# Filter-11.net
KiCad netlist of a schematic drawn in Altium Designer
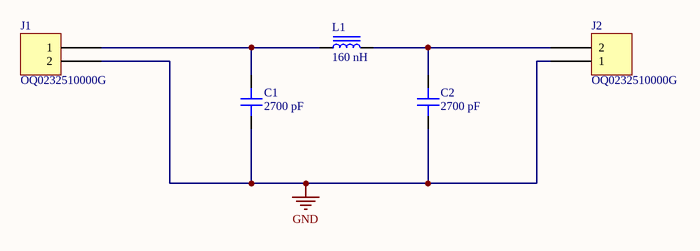
[diagram p0: Filter-11.SchDoc]

(export (version "E")
  (design (tool "Eeschema 10.0.6"))
  (components
    (comp (ref "C1")
      (value "2700 pF")
      (footprint "CAP 0603_1608")
      (description "CAP CER 2700PF 25V NP0 0603")
      (fields (field (name "PART NUMBER") "C0603C272F3GAC7867") (field (name "MANUFACTURER") "KEMET"))
      (libsource (lib "Celestial Altium Library - altium_library") (part "Capacitor"))
    )
    (comp (ref "C2")
      (value "2700 pF")
      (footprint "CAP 0603_1608")
      (description "CAP CER 2700PF 25V NP0 0603")
      (fields (field (name "PART NUMBER") "C0603C272F3GAC7867") (field (name "MANUFACTURER") "KEMET"))
      (libsource (lib "Celestial Altium Library - altium_library") (part "Capacitor"))
    )
    (comp (ref "J1")
      (value "OQ0232510000G")
      (footprint "FCI 06-381-2PIN")
      (description "TERM BLOCK HDR 2POS 90DEG 3.81MM")
      (fields (field (name "MANUFACTURER") "Amphenol Anytek"))
      (libsource (lib "") (part "2 Pin_1"))
    )
    (comp (ref "J2")
      (value "OQ0232510000G")
      (footprint "FCI 06-381-2PIN")
      (description "TERM BLOCK HDR 2POS 90DEG 3.81MM")
      (fields (field (name "MANUFACTURER") "Amphenol Anytek"))
      (libsource (lib "Celestial Altium Library - altium_library") (part "2 Pin"))
    )
    (comp (ref "L1")
      (value "160 nH")
      (footprint "IND 0402_1005 RF WW")
      (description "FIXED IND 160NH 480MA 330MOHM SM")
      (fields
        (field (name "PART NUMBER") "LQW15CNR16J00D")
        (field (name "MANUFACTURER") "Murata Electronics")
      )
      (libsource (lib "Celestial Altium Library - altium_library") (part "Inductor"))
    )
  )
  (nets
    (net (code "1") (name "GND") (class "Default")
      (node (ref "C1") (pin "1") (pinfunction "1_1") (pintype "passive"))
      (node (ref "C2") (pin "1") (pinfunction "1_1") (pintype "passive"))
      (node (ref "J1") (pin "2") (pinfunction "2_2") (pintype "passive"))
      (node (ref "J2") (pin "1") (pinfunction "1_1") (pintype "passive"))
    )
    (net (code "2") (name "Net-(C1-Pad2)") (class "Default")
      (node (ref "C1") (pin "2") (pinfunction "2_2") (pintype "passive"))
      (node (ref "J1") (pin "1") (pinfunction "1_1") (pintype "passive"))
      (node (ref "L1") (pin "1") (pinfunction "1_1") (pintype "passive"))
    )
    (net (code "3") (name "Net-(C2-Pad2)") (class "Default")
      (node (ref "C2") (pin "2") (pinfunction "2_2") (pintype "passive"))
      (node (ref "J2") (pin "2") (pinfunction "2_2") (pintype "passive"))
      (node (ref "L1") (pin "2") (pinfunction "2_2") (pintype "passive"))
    )
  )
)
